# tester_board.net
KiCad netlist of a schematic drawn in EAGLE
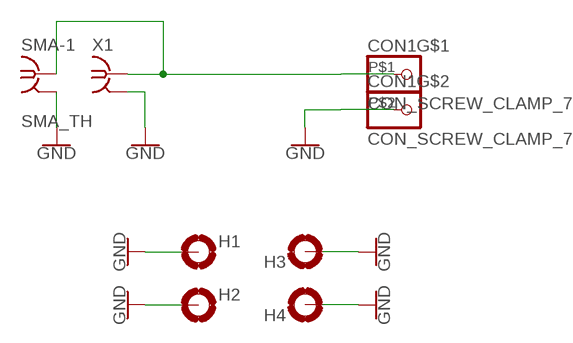
[diagram p0: schematic, sheet 1]

(export (version "E")
  (design (tool "Eeschema 10.0.6"))
  (components
    (comp (ref "CON1")
      (value "CON_SCREW_CLAMP_7MM")
      (footprint "eagle-import:CON_SCREW_CLAMP_7MM")
      (libsource (lib "eagle-import") (part "CON_SCREW_CLAMP_7MM"))
    )
    (comp (ref "H1")
      (value "MOUNT-PAD-ROUND3.0")
      (footprint "eagle-import:3,0-PAD")
      (libsource (lib "eagle-import") (part "MOUNT-PAD-ROUND3.0"))
    )
    (comp (ref "H2")
      (value "MOUNT-PAD-ROUND3.0")
      (footprint "eagle-import:3,0-PAD")
      (libsource (lib "eagle-import") (part "MOUNT-PAD-ROUND3.0"))
    )
    (comp (ref "H3")
      (value "MOUNT-PAD-ROUND3.0")
      (footprint "eagle-import:3,0-PAD")
      (libsource (lib "eagle-import") (part "MOUNT-PAD-ROUND3.0"))
    )
    (comp (ref "H4")
      (value "MOUNT-PAD-ROUND3.0")
      (footprint "eagle-import:3,0-PAD")
      (libsource (lib "eagle-import") (part "MOUNT-PAD-ROUND3.0"))
    )
    (comp (ref "SMA-1")
      (value "SMA_TH")
      (footprint "eagle-import:BU-SMA-V")
      (libsource (lib "eagle-import") (part "SMA_TH"))
    )
    (comp (ref "X1")
      (value "SMA-142-0711-821/826")
      (footprint "eagle-import:J502-ND-142-0711-821_826")
      (fields (field (name "MF") "JOHNSON COMPONENTS") (field (name "MPN") "142-0711-821"))
      (libsource (lib "eagle-import") (part "SMA-142-0711-821/826"))
    )
  )
  (nets
    (net (code "1") (name "GND") (class "Default")
      (node (ref "CON1") (pin "P$2") (pinfunction "1_P$2") (pintype "passive"))
      (node (ref "H1") (pin "B3,0") (pinfunction "MOUNT_B3,0") (pintype "passive"))
      (node (ref "H2") (pin "B3,0") (pinfunction "MOUNT_B3,0") (pintype "passive"))
      (node (ref "H3") (pin "B3,0") (pinfunction "MOUNT_B3,0") (pintype "passive"))
      (node (ref "H4") (pin "B3,0") (pinfunction "MOUNT_B3,0") (pintype "passive"))
      (node (ref "SMA-1") (pin "2") (pinfunction "GND_2") (pintype "passive"))
      (node (ref "SMA-1") (pin "3") (pinfunction "GND_3") (pintype "passive"))
      (node (ref "SMA-1") (pin "4") (pinfunction "GND_4") (pintype "passive"))
      (node (ref "SMA-1") (pin "5") (pinfunction "GND_5") (pintype "passive"))
      (node (ref "X1") (pin "G@1") (pinfunction "2_G@1") (pintype "passive"))
      (node (ref "X1") (pin "G@2") (pinfunction "2_G@2") (pintype "passive"))
      (node (ref "X1") (pin "G@3") (pinfunction "2_G@3") (pintype "passive"))
      (node (ref "X1") (pin "G@4") (pinfunction "2_G@4") (pintype "passive"))
    )
    (net (code "2") (name "Net-(CON1A-1)") (class "Default")
      (node (ref "CON1") (pin "P$1") (pinfunction "1_P$1") (pintype "passive"))
      (node (ref "SMA-1") (pin "1") (pinfunction "1_1") (pintype "passive"))
      (node (ref "X1") (pin "1") (pinfunction "1_1") (pintype "passive"))
    )
  )
)
